# snes_visualization_shoulder.net
KiCad netlist of a schematic drawn in EAGLE
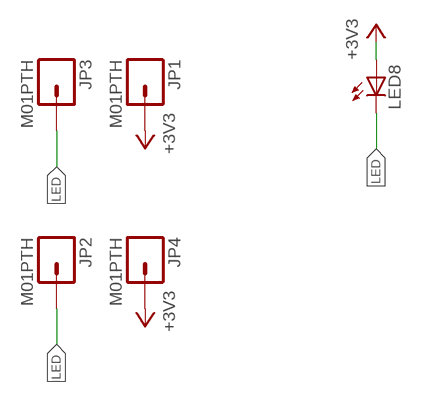
[diagram p0: schematic, sheet 1]

(export (version "E")
  (design (tool "Eeschema 10.0.6"))
  (components
    (comp (ref "JP1")
      (value "M01PTH")
      (footprint "eagle-import:1X01")
      (libsource (lib "eagle-import") (part "M01PTH"))
    )
    (comp (ref "JP2")
      (value "M01PTH")
      (footprint "eagle-import:1X01")
      (libsource (lib "eagle-import") (part "M01PTH"))
    )
    (comp (ref "JP3")
      (value "M01PTH")
      (footprint "eagle-import:1X01")
      (libsource (lib "eagle-import") (part "M01PTH"))
    )
    (comp (ref "JP4")
      (value "M01PTH")
      (footprint "eagle-import:1X01")
      (libsource (lib "eagle-import") (part "M01PTH"))
    )
    (comp (ref "LED8")
      (value "LED5MM")
      (footprint "eagle-import:LED5MM")
      (libsource (lib "eagle-import") (part "LED5MM"))
    )
  )
  (nets
    (net (code "1") (name "+3V3") (class "Default")
      (node (ref "JP1") (pin "1") (pinfunction "1_1") (pintype "passive"))
      (node (ref "JP4") (pin "1") (pinfunction "1_1") (pintype "passive"))
      (node (ref "LED8") (pin "A") (pinfunction "A_A") (pintype "passive"))
    )
    (net (code "2") (name "LED") (class "Default")
      (node (ref "JP2") (pin "1") (pinfunction "1_1") (pintype "passive"))
      (node (ref "JP3") (pin "1") (pinfunction "1_1") (pintype "passive"))
      (node (ref "LED8") (pin "K") (pinfunction "C_K") (pintype "passive"))
    )
  )
)
